# fpga22-serdes-power.net
KiCad netlist of a schematic drawn in Altium Designer
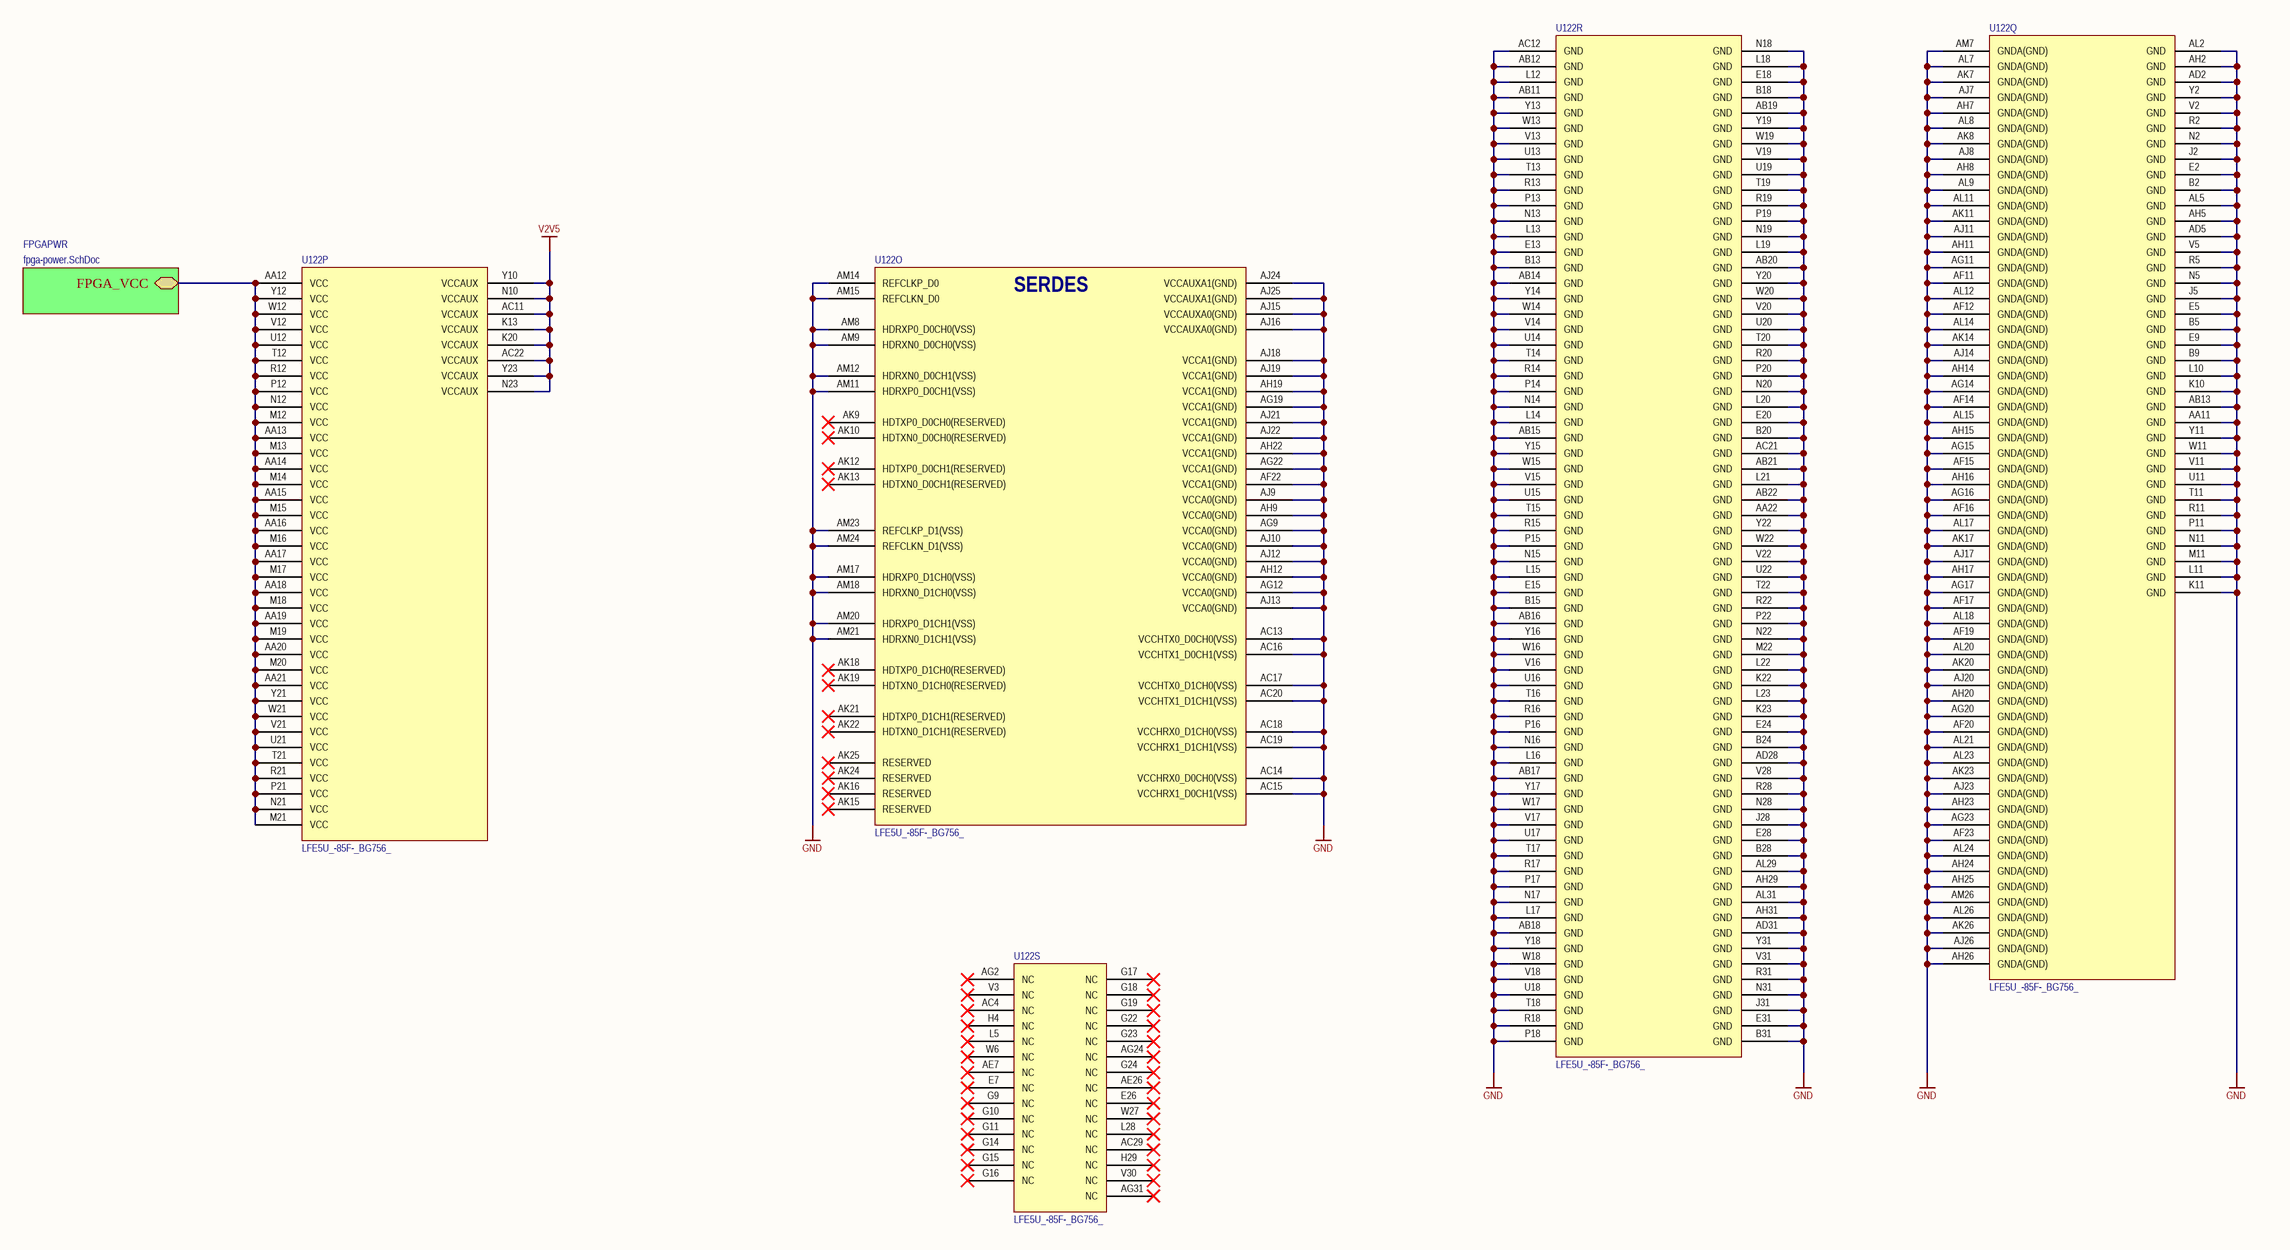
[diagram p0: fpga22-serdes-power.SchDoc]

(export (version "E")
  (design (tool "Eeschema 10.0.6"))
  (components
    (comp (ref "U122")
      (value "LFE5U_-85F-_BG756_")
      (footprint "lattice:caBGA756")
      (description "ECP5 FPGA, 85k LUT, 756-caBGA")
      (fields (field (name "MANUFACTURER") "Lattice Semiconductor"))
      (libsource (lib "lattice") (part "LFE5U_-85F-_BG756_"))
    )
  )
  (nets
    (net (code "1") (name "/FPGA_VCC") (class "Default")
      (node (ref "U122") (pin "AA12") (pinfunction "VCC_AA12") (pintype "power_in"))
      (node (ref "U122") (pin "AA13") (pinfunction "VCC_AA13") (pintype "power_in"))
      (node (ref "U122") (pin "AA14") (pinfunction "VCC_AA14") (pintype "power_in"))
      (node (ref "U122") (pin "AA15") (pinfunction "VCC_AA15") (pintype "power_in"))
      (node (ref "U122") (pin "AA16") (pinfunction "VCC_AA16") (pintype "power_in"))
      (node (ref "U122") (pin "AA17") (pinfunction "VCC_AA17") (pintype "power_in"))
      (node (ref "U122") (pin "AA18") (pinfunction "VCC_AA18") (pintype "power_in"))
      (node (ref "U122") (pin "AA19") (pinfunction "VCC_AA19") (pintype "power_in"))
      (node (ref "U122") (pin "AA20") (pinfunction "VCC_AA20") (pintype "power_in"))
      (node (ref "U122") (pin "AA21") (pinfunction "VCC_AA21") (pintype "power_in"))
      (node (ref "U122") (pin "M12") (pinfunction "VCC_M12") (pintype "power_in"))
      (node (ref "U122") (pin "M13") (pinfunction "VCC_M13") (pintype "power_in"))
      (node (ref "U122") (pin "M14") (pinfunction "VCC_M14") (pintype "power_in"))
      (node (ref "U122") (pin "M15") (pinfunction "VCC_M15") (pintype "power_in"))
      (node (ref "U122") (pin "M16") (pinfunction "VCC_M16") (pintype "power_in"))
      (node (ref "U122") (pin "M17") (pinfunction "VCC_M17") (pintype "power_in"))
      (node (ref "U122") (pin "M18") (pinfunction "VCC_M18") (pintype "power_in"))
      (node (ref "U122") (pin "M19") (pinfunction "VCC_M19") (pintype "power_in"))
      (node (ref "U122") (pin "M20") (pinfunction "VCC_M20") (pintype "power_in"))
      (node (ref "U122") (pin "M21") (pinfunction "VCC_M21") (pintype "power_in"))
      (node (ref "U122") (pin "N12") (pinfunction "VCC_N12") (pintype "power_in"))
      (node (ref "U122") (pin "N21") (pinfunction "VCC_N21") (pintype "power_in"))
      (node (ref "U122") (pin "P12") (pinfunction "VCC_P12") (pintype "power_in"))
      (node (ref "U122") (pin "P21") (pinfunction "VCC_P21") (pintype "power_in"))
      (node (ref "U122") (pin "R12") (pinfunction "VCC_R12") (pintype "power_in"))
      (node (ref "U122") (pin "R21") (pinfunction "VCC_R21") (pintype "power_in"))
      (node (ref "U122") (pin "T12") (pinfunction "VCC_T12") (pintype "power_in"))
      (node (ref "U122") (pin "T21") (pinfunction "VCC_T21") (pintype "power_in"))
      (node (ref "U122") (pin "U12") (pinfunction "VCC_U12") (pintype "power_in"))
      (node (ref "U122") (pin "U21") (pinfunction "VCC_U21") (pintype "power_in"))
      (node (ref "U122") (pin "V12") (pinfunction "VCC_V12") (pintype "power_in"))
      (node (ref "U122") (pin "V21") (pinfunction "VCC_V21") (pintype "power_in"))
      (node (ref "U122") (pin "W12") (pinfunction "VCC_W12") (pintype "power_in"))
      (node (ref "U122") (pin "W21") (pinfunction "VCC_W21") (pintype "power_in"))
      (node (ref "U122") (pin "Y12") (pinfunction "VCC_Y12") (pintype "power_in"))
      (node (ref "U122") (pin "Y21") (pinfunction "VCC_Y21") (pintype "power_in"))
    )
    (net (code "2") (name "GND") (class "Default")
      (node (ref "U122") (pin "AA11") (pinfunction "GND_AA11") (pintype "power_in"))
      (node (ref "U122") (pin "AA22") (pinfunction "GND_AA22") (pintype "power_in"))
      (node (ref "U122") (pin "AB11") (pinfunction "GND_AB11") (pintype "power_in"))
      (node (ref "U122") (pin "AB12") (pinfunction "GND_AB12") (pintype "power_in"))
      (node (ref "U122") (pin "AB13") (pinfunction "GND_AB13") (pintype "power_in"))
      (node (ref "U122") (pin "AB14") (pinfunction "GND_AB14") (pintype "power_in"))
      (node (ref "U122") (pin "AB15") (pinfunction "GND_AB15") (pintype "power_in"))
      (node (ref "U122") (pin "AB16") (pinfunction "GND_AB16") (pintype "power_in"))
      (node (ref "U122") (pin "AB17") (pinfunction "GND_AB17") (pintype "power_in"))
      (node (ref "U122") (pin "AB18") (pinfunction "GND_AB18") (pintype "power_in"))
      (node (ref "U122") (pin "AB19") (pinfunction "GND_AB19") (pintype "power_in"))
      (node (ref "U122") (pin "AB20") (pinfunction "GND_AB20") (pintype "power_in"))
      (node (ref "U122") (pin "AB21") (pinfunction "GND_AB21") (pintype "power_in"))
      (node (ref "U122") (pin "AB22") (pinfunction "GND_AB22") (pintype "power_in"))
      (node (ref "U122") (pin "AC12") (pinfunction "GND_AC12") (pintype "power_in"))
      (node (ref "U122") (pin "AC13") (pinfunction "VCCHTX0_D0CH0(VSS)_AC13") (pintype "power_in"))
      (node (ref "U122") (pin "AC14") (pinfunction "VCCHRX0_D0CH0(VSS)_AC14") (pintype "power_in"))
      (node (ref "U122") (pin "AC15") (pinfunction "VCCHRX1_D0CH1(VSS)_AC15") (pintype "power_in"))
      (node (ref "U122") (pin "AC16") (pinfunction "VCCHTX1_D0CH1(VSS)_AC16") (pintype "power_in"))
      (node (ref "U122") (pin "AC17") (pinfunction "VCCHTX0_D1CH0(VSS)_AC17") (pintype "power_in"))
      (node (ref "U122") (pin "AC18") (pinfunction "VCCHRX0_D1CH0(VSS)_AC18") (pintype "power_in"))
      (node (ref "U122") (pin "AC19") (pinfunction "VCCHRX1_D1CH1(VSS)_AC19") (pintype "power_in"))
      (node (ref "U122") (pin "AC20") (pinfunction "VCCHTX1_D1CH1(VSS)_AC20") (pintype "power_in"))
      (node (ref "U122") (pin "AC21") (pinfunction "GND_AC21") (pintype "power_in"))
      (node (ref "U122") (pin "AD2") (pinfunction "GND_AD2") (pintype "power_in"))
      (node (ref "U122") (pin "AD28") (pinfunction "GND_AD28") (pintype "power_in"))
      (node (ref "U122") (pin "AD31") (pinfunction "GND_AD31") (pintype "power_in"))
      (node (ref "U122") (pin "AD5") (pinfunction "GND_AD5") (pintype "power_in"))
      (node (ref "U122") (pin "AF11") (pinfunction "GNDA(GND)_AF11") (pintype "power_in"))
      (node (ref "U122") (pin "AF12") (pinfunction "GNDA(GND)_AF12") (pintype "power_in"))
      (node (ref "U122") (pin "AF14") (pinfunction "GNDA(GND)_AF14") (pintype "power_in"))
      (node (ref "U122") (pin "AF15") (pinfunction "GNDA(GND)_AF15") (pintype "power_in"))
      (node (ref "U122") (pin "AF16") (pinfunction "GNDA(GND)_AF16") (pintype "power_in"))
      (node (ref "U122") (pin "AF17") (pinfunction "GNDA(GND)_AF17") (pintype "power_in"))
      (node (ref "U122") (pin "AF19") (pinfunction "GNDA(GND)_AF19") (pintype "power_in"))
      (node (ref "U122") (pin "AF20") (pinfunction "GNDA(GND)_AF20") (pintype "power_in"))
      (node (ref "U122") (pin "AF22") (pinfunction "VCCA1(GND)_AF22") (pintype "power_in"))
      (node (ref "U122") (pin "AF23") (pinfunction "GNDA(GND)_AF23") (pintype "power_in"))
      (node (ref "U122") (pin "AG11") (pinfunction "GNDA(GND)_AG11") (pintype "power_in"))
      (node (ref "U122") (pin "AG12") (pinfunction "VCCA0(GND)_AG12") (pintype "power_in"))
      (node (ref "U122") (pin "AG14") (pinfunction "GNDA(GND)_AG14") (pintype "power_in"))
      (node (ref "U122") (pin "AG15") (pinfunction "GNDA(GND)_AG15") (pintype "power_in"))
      (node (ref "U122") (pin "AG16") (pinfunction "GNDA(GND)_AG16") (pintype "power_in"))
      (node (ref "U122") (pin "AG17") (pinfunction "GNDA(GND)_AG17") (pintype "power_in"))
      (node (ref "U122") (pin "AG19") (pinfunction "VCCA1(GND)_AG19") (pintype "power_in"))
      (node (ref "U122") (pin "AG20") (pinfunction "GNDA(GND)_AG20") (pintype "power_in"))
      (node (ref "U122") (pin "AG22") (pinfunction "VCCA1(GND)_AG22") (pintype "power_in"))
      (node (ref "U122") (pin "AG23") (pinfunction "GNDA(GND)_AG23") (pintype "power_in"))
      (node (ref "U122") (pin "AG9") (pinfunction "VCCA0(GND)_AG9") (pintype "power_in"))
      (node (ref "U122") (pin "AH11") (pinfunction "GNDA(GND)_AH11") (pintype "power_in"))
      (node (ref "U122") (pin "AH12") (pinfunction "VCCA0(GND)_AH12") (pintype "power_in"))
      (node (ref "U122") (pin "AH14") (pinfunction "GNDA(GND)_AH14") (pintype "power_in"))
      (node (ref "U122") (pin "AH15") (pinfunction "GNDA(GND)_AH15") (pintype "power_in"))
      (node (ref "U122") (pin "AH16") (pinfunction "GNDA(GND)_AH16") (pintype "power_in"))
      (node (ref "U122") (pin "AH17") (pinfunction "GNDA(GND)_AH17") (pintype "power_in"))
      (node (ref "U122") (pin "AH19") (pinfunction "VCCA1(GND)_AH19") (pintype "power_in"))
      (node (ref "U122") (pin "AH2") (pinfunction "GND_AH2") (pintype "power_in"))
      (node (ref "U122") (pin "AH20") (pinfunction "GNDA(GND)_AH20") (pintype "power_in"))
      (node (ref "U122") (pin "AH22") (pinfunction "VCCA1(GND)_AH22") (pintype "power_in"))
      (node (ref "U122") (pin "AH23") (pinfunction "GNDA(GND)_AH23") (pintype "power_in"))
      (node (ref "U122") (pin "AH24") (pinfunction "GNDA(GND)_AH24") (pintype "power_in"))
      (node (ref "U122") (pin "AH25") (pinfunction "GNDA(GND)_AH25") (pintype "power_in"))
      (node (ref "U122") (pin "AH26") (pinfunction "GNDA(GND)_AH26") (pintype "power_in"))
      (node (ref "U122") (pin "AH29") (pinfunction "GND_AH29") (pintype "power_in"))
      (node (ref "U122") (pin "AH31") (pinfunction "GND_AH31") (pintype "power_in"))
      (node (ref "U122") (pin "AH5") (pinfunction "GND_AH5") (pintype "power_in"))
      (node (ref "U122") (pin "AH7") (pinfunction "GNDA(GND)_AH7") (pintype "power_in"))
      (node (ref "U122") (pin "AH8") (pinfunction "GNDA(GND)_AH8") (pintype "power_in"))
      (node (ref "U122") (pin "AH9") (pinfunction "VCCA0(GND)_AH9") (pintype "power_in"))
      (node (ref "U122") (pin "AJ10") (pinfunction "VCCA0(GND)_AJ10") (pintype "power_in"))
      (node (ref "U122") (pin "AJ11") (pinfunction "GNDA(GND)_AJ11") (pintype "power_in"))
      (node (ref "U122") (pin "AJ12") (pinfunction "VCCA0(GND)_AJ12") (pintype "power_in"))
      (node (ref "U122") (pin "AJ13") (pinfunction "VCCA0(GND)_AJ13") (pintype "power_in"))
      (node (ref "U122") (pin "AJ14") (pinfunction "GNDA(GND)_AJ14") (pintype "power_in"))
      (node (ref "U122") (pin "AJ15") (pinfunction "VCCAUXA0(GND)_AJ15") (pintype "power_in"))
      (node (ref "U122") (pin "AJ16") (pinfunction "VCCAUXA0(GND)_AJ16") (pintype "power_in"))
      (node (ref "U122") (pin "AJ17") (pinfunction "GNDA(GND)_AJ17") (pintype "power_in"))
      (node (ref "U122") (pin "AJ18") (pinfunction "VCCA1(GND)_AJ18") (pintype "power_in"))
      (node (ref "U122") (pin "AJ19") (pinfunction "VCCA1(GND)_AJ19") (pintype "power_in"))
      (node (ref "U122") (pin "AJ20") (pinfunction "GNDA(GND)_AJ20") (pintype "power_in"))
      (node (ref "U122") (pin "AJ21") (pinfunction "VCCA1(GND)_AJ21") (pintype "power_in"))
      (node (ref "U122") (pin "AJ22") (pinfunction "VCCA1(GND)_AJ22") (pintype "power_in"))
      (node (ref "U122") (pin "AJ23") (pinfunction "GNDA(GND)_AJ23") (pintype "power_in"))
      (node (ref "U122") (pin "AJ24") (pinfunction "VCCAUXA1(GND)_AJ24") (pintype "power_in"))
      (node (ref "U122") (pin "AJ25") (pinfunction "VCCAUXA1(GND)_AJ25") (pintype "power_in"))
      (node (ref "U122") (pin "AJ26") (pinfunction "GNDA(GND)_AJ26") (pintype "power_in"))
      (node (ref "U122") (pin "AJ7") (pinfunction "GNDA(GND)_AJ7") (pintype "power_in"))
      (node (ref "U122") (pin "AJ8") (pinfunction "GNDA(GND)_AJ8") (pintype "power_in"))
      (node (ref "U122") (pin "AJ9") (pinfunction "VCCA0(GND)_AJ9") (pintype "power_in"))
      (node (ref "U122") (pin "AK11") (pinfunction "GNDA(GND)_AK11") (pintype "power_in"))
      (node (ref "U122") (pin "AK14") (pinfunction "GNDA(GND)_AK14") (pintype "power_in"))
      (node (ref "U122") (pin "AK17") (pinfunction "GNDA(GND)_AK17") (pintype "power_in"))
      (node (ref "U122") (pin "AK20") (pinfunction "GNDA(GND)_AK20") (pintype "power_in"))
      (node (ref "U122") (pin "AK23") (pinfunction "GNDA(GND)_AK23") (pintype "power_in"))
      (node (ref "U122") (pin "AK26") (pinfunction "GNDA(GND)_AK26") (pintype "power_in"))
      (node (ref "U122") (pin "AK7") (pinfunction "GNDA(GND)_AK7") (pintype "power_in"))
      (node (ref "U122") (pin "AK8") (pinfunction "GNDA(GND)_AK8") (pintype "power_in"))
      (node (ref "U122") (pin "AL11") (pinfunction "GNDA(GND)_AL11") (pintype "power_in"))
      (node (ref "U122") (pin "AL12") (pinfunction "GNDA(GND)_AL12") (pintype "power_in"))
      (node (ref "U122") (pin "AL14") (pinfunction "GNDA(GND)_AL14") (pintype "power_in"))
      (node (ref "U122") (pin "AL15") (pinfunction "GNDA(GND)_AL15") (pintype "power_in"))
      (node (ref "U122") (pin "AL17") (pinfunction "GNDA(GND)_AL17") (pintype "power_in"))
      (node (ref "U122") (pin "AL18") (pinfunction "GNDA(GND)_AL18") (pintype "power_in"))
      (node (ref "U122") (pin "AL2") (pinfunction "GND_AL2") (pintype "power_in"))
      (node (ref "U122") (pin "AL20") (pinfunction "GNDA(GND)_AL20") (pintype "power_in"))
      (node (ref "U122") (pin "AL21") (pinfunction "GNDA(GND)_AL21") (pintype "power_in"))
      (node (ref "U122") (pin "AL23") (pinfunction "GNDA(GND)_AL23") (pintype "power_in"))
      (node (ref "U122") (pin "AL24") (pinfunction "GNDA(GND)_AL24") (pintype "power_in"))
      (node (ref "U122") (pin "AL26") (pinfunction "GNDA(GND)_AL26") (pintype "power_in"))
      (node (ref "U122") (pin "AL29") (pinfunction "GND_AL29") (pintype "power_in"))
      (node (ref "U122") (pin "AL31") (pinfunction "GND_AL31") (pintype "power_in"))
      (node (ref "U122") (pin "AL5") (pinfunction "GND_AL5") (pintype "power_in"))
      (node (ref "U122") (pin "AL7") (pinfunction "GNDA(GND)_AL7") (pintype "power_in"))
      (node (ref "U122") (pin "AL8") (pinfunction "GNDA(GND)_AL8") (pintype "power_in"))
      (node (ref "U122") (pin "AL9") (pinfunction "GNDA(GND)_AL9") (pintype "power_in"))
      (node (ref "U122") (pin "AM11") (pinfunction "HDRXP0_D0CH1(VSS)_AM11") (pintype "passive"))
      (node (ref "U122") (pin "AM12") (pinfunction "HDRXN0_D0CH1(VSS)_AM12") (pintype "passive"))
      (node (ref "U122") (pin "AM14") (pinfunction "REFCLKP_D0_AM14") (pintype "passive"))
      (node (ref "U122") (pin "AM15") (pinfunction "REFCLKN_D0_AM15") (pintype "passive"))
      (node (ref "U122") (pin "AM17") (pinfunction "HDRXP0_D1CH0(VSS)_AM17") (pintype "passive"))
      (node (ref "U122") (pin "AM18") (pinfunction "HDRXN0_D1CH0(VSS)_AM18") (pintype "passive"))
      (node (ref "U122") (pin "AM20") (pinfunction "HDRXP0_D1CH1(VSS)_AM20") (pintype "passive"))
      (node (ref "U122") (pin "AM21") (pinfunction "HDRXN0_D1CH1(VSS)_AM21") (pintype "passive"))
      (node (ref "U122") (pin "AM23") (pinfunction "REFCLKP_D1(VSS)_AM23") (pintype "passive"))
      (node (ref "U122") (pin "AM24") (pinfunction "REFCLKN_D1(VSS)_AM24") (pintype "passive"))
      (node (ref "U122") (pin "AM26") (pinfunction "GNDA(GND)_AM26") (pintype "power_in"))
      (node (ref "U122") (pin "AM7") (pinfunction "GNDA(GND)_AM7") (pintype "power_in"))
      (node (ref "U122") (pin "AM8") (pinfunction "HDRXP0_D0CH0(VSS)_AM8") (pintype "passive"))
      (node (ref "U122") (pin "AM9") (pinfunction "HDRXN0_D0CH0(VSS)_AM9") (pintype "passive"))
      (node (ref "U122") (pin "B13") (pinfunction "GND_B13") (pintype "power_in"))
      (node (ref "U122") (pin "B15") (pinfunction "GND_B15") (pintype "power_in"))
      (node (ref "U122") (pin "B18") (pinfunction "GND_B18") (pintype "power_in"))
      (node (ref "U122") (pin "B2") (pinfunction "GND_B2") (pintype "power_in"))
      (node (ref "U122") (pin "B20") (pinfunction "GND_B20") (pintype "power_in"))
      (node (ref "U122") (pin "B24") (pinfunction "GND_B24") (pintype "power_in"))
      (node (ref "U122") (pin "B28") (pinfunction "GND_B28") (pintype "power_in"))
      (node (ref "U122") (pin "B31") (pinfunction "GND_B31") (pintype "power_in"))
      (node (ref "U122") (pin "B5") (pinfunction "GND_B5") (pintype "power_in"))
      (node (ref "U122") (pin "B9") (pinfunction "GND_B9") (pintype "power_in"))
      (node (ref "U122") (pin "E13") (pinfunction "GND_E13") (pintype "power_in"))
      (node (ref "U122") (pin "E15") (pinfunction "GND_E15") (pintype "power_in"))
      (node (ref "U122") (pin "E18") (pinfunction "GND_E18") (pintype "power_in"))
      (node (ref "U122") (pin "E2") (pinfunction "GND_E2") (pintype "power_in"))
      (node (ref "U122") (pin "E20") (pinfunction "GND_E20") (pintype "power_in"))
      (node (ref "U122") (pin "E24") (pinfunction "GND_E24") (pintype "power_in"))
      (node (ref "U122") (pin "E28") (pinfunction "GND_E28") (pintype "power_in"))
      (node (ref "U122") (pin "E31") (pinfunction "GND_E31") (pintype "power_in"))
      (node (ref "U122") (pin "E5") (pinfunction "GND_E5") (pintype "power_in"))
      (node (ref "U122") (pin "E9") (pinfunction "GND_E9") (pintype "power_in"))
      (node (ref "U122") (pin "J2") (pinfunction "GND_J2") (pintype "power_in"))
      (node (ref "U122") (pin "J28") (pinfunction "GND_J28") (pintype "power_in"))
      (node (ref "U122") (pin "J31") (pinfunction "GND_J31") (pintype "power_in"))
      (node (ref "U122") (pin "J5") (pinfunction "GND_J5") (pintype "power_in"))
      (node (ref "U122") (pin "K10") (pinfunction "GND_K10") (pintype "power_in"))
      (node (ref "U122") (pin "K11") (pinfunction "GND_K11") (pintype "power_in"))
      (node (ref "U122") (pin "K22") (pinfunction "GND_K22") (pintype "power_in"))
      (node (ref "U122") (pin "K23") (pinfunction "GND_K23") (pintype "power_in"))
      (node (ref "U122") (pin "L10") (pinfunction "GND_L10") (pintype "power_in"))
      (node (ref "U122") (pin "L11") (pinfunction "GND_L11") (pintype "power_in"))
      (node (ref "U122") (pin "L12") (pinfunction "GND_L12") (pintype "power_in"))
      (node (ref "U122") (pin "L13") (pinfunction "GND_L13") (pintype "power_in"))
      (node (ref "U122") (pin "L14") (pinfunction "GND_L14") (pintype "power_in"))
      (node (ref "U122") (pin "L15") (pinfunction "GND_L15") (pintype "power_in"))
      (node (ref "U122") (pin "L16") (pinfunction "GND_L16") (pintype "power_in"))
      (node (ref "U122") (pin "L17") (pinfunction "GND_L17") (pintype "power_in"))
      (node (ref "U122") (pin "L18") (pinfunction "GND_L18") (pintype "power_in"))
      (node (ref "U122") (pin "L19") (pinfunction "GND_L19") (pintype "power_in"))
      (node (ref "U122") (pin "L20") (pinfunction "GND_L20") (pintype "power_in"))
      (node (ref "U122") (pin "L21") (pinfunction "GND_L21") (pintype "power_in"))
      (node (ref "U122") (pin "L22") (pinfunction "GND_L22") (pintype "power_in"))
      (node (ref "U122") (pin "L23") (pinfunction "GND_L23") (pintype "power_in"))
      (node (ref "U122") (pin "M11") (pinfunction "GND_M11") (pintype "power_in"))
      (node (ref "U122") (pin "M22") (pinfunction "GND_M22") (pintype "power_in"))
      (node (ref "U122") (pin "N11") (pinfunction "GND_N11") (pintype "power_in"))
      (node (ref "U122") (pin "N13") (pinfunction "GND_N13") (pintype "power_in"))
      (node (ref "U122") (pin "N14") (pinfunction "GND_N14") (pintype "power_in"))
      (node (ref "U122") (pin "N15") (pinfunction "GND_N15") (pintype "power_in"))
      (node (ref "U122") (pin "N16") (pinfunction "GND_N16") (pintype "power_in"))
      (node (ref "U122") (pin "N17") (pinfunction "GND_N17") (pintype "power_in"))
      (node (ref "U122") (pin "N18") (pinfunction "GND_N18") (pintype "power_in"))
      (node (ref "U122") (pin "N19") (pinfunction "GND_N19") (pintype "power_in"))
      (node (ref "U122") (pin "N2") (pinfunction "GND_N2") (pintype "power_in"))
      (node (ref "U122") (pin "N20") (pinfunction "GND_N20") (pintype "power_in"))
      (node (ref "U122") (pin "N22") (pinfunction "GND_N22") (pintype "power_in"))
      (node (ref "U122") (pin "N28") (pinfunction "GND_N28") (pintype "power_in"))
      (node (ref "U122") (pin "N31") (pinfunction "GND_N31") (pintype "power_in"))
      (node (ref "U122") (pin "N5") (pinfunction "GND_N5") (pintype "power_in"))
      (node (ref "U122") (pin "P11") (pinfunction "GND_P11") (pintype "power_in"))
      (node (ref "U122") (pin "P13") (pinfunction "GND_P13") (pintype "power_in"))
      (node (ref "U122") (pin "P14") (pinfunction "GND_P14") (pintype "power_in"))
      (node (ref "U122") (pin "P15") (pinfunction "GND_P15") (pintype "power_in"))
      (node (ref "U122") (pin "P16") (pinfunction "GND_P16") (pintype "power_in"))
      (node (ref "U122") (pin "P17") (pinfunction "GND_P17") (pintype "power_in"))
      (node (ref "U122") (pin "P18") (pinfunction "GND_P18") (pintype "power_in"))
      (node (ref "U122") (pin "P19") (pinfunction "GND_P19") (pintype "power_in"))
      (node (ref "U122") (pin "P20") (pinfunction "GND_P20") (pintype "power_in"))
      (node (ref "U122") (pin "P22") (pinfunction "GND_P22") (pintype "power_in"))
      (node (ref "U122") (pin "R11") (pinfunction "GND_R11") (pintype "power_in"))
      (node (ref "U122") (pin "R13") (pinfunction "GND_R13") (pintype "power_in"))
      (node (ref "U122") (pin "R14") (pinfunction "GND_R14") (pintype "power_in"))
      (node (ref "U122") (pin "R15") (pinfunction "GND_R15") (pintype "power_in"))
      (node (ref "U122") (pin "R16") (pinfunction "GND_R16") (pintype "power_in"))
      (node (ref "U122") (pin "R17") (pinfunction "GND_R17") (pintype "power_in"))
      (node (ref "U122") (pin "R18") (pinfunction "GND_R18") (pintype "power_in"))
      (node (ref "U122") (pin "R19") (pinfunction "GND_R19") (pintype "power_in"))
      (node (ref "U122") (pin "R2") (pinfunction "GND_R2") (pintype "power_in"))
      (node (ref "U122") (pin "R20") (pinfunction "GND_R20") (pintype "power_in"))
      (node (ref "U122") (pin "R22") (pinfunction "GND_R22") (pintype "power_in"))
      (node (ref "U122") (pin "R28") (pinfunction "GND_R28") (pintype "power_in"))
      (node (ref "U122") (pin "R31") (pinfunction "GND_R31") (pintype "power_in"))
      (node (ref "U122") (pin "R5") (pinfunction "GND_R5") (pintype "power_in"))
      (node (ref "U122") (pin "T11") (pinfunction "GND_T11") (pintype "power_in"))
      (node (ref "U122") (pin "T13") (pinfunction "GND_T13") (pintype "power_in"))
      (node (ref "U122") (pin "T14") (pinfunction "GND_T14") (pintype "power_in"))
      (node (ref "U122") (pin "T15") (pinfunction "GND_T15") (pintype "power_in"))
      (node (ref "U122") (pin "T16") (pinfunction "GND_T16") (pintype "power_in"))
      (node (ref "U122") (pin "T17") (pinfunction "GND_T17") (pintype "power_in"))
      (node (ref "U122") (pin "T18") (pinfunction "GND_T18") (pintype "power_in"))
      (node (ref "U122") (pin "T19") (pinfunction "GND_T19") (pintype "power_in"))
      (node (ref "U122") (pin "T20") (pinfunction "GND_T20") (pintype "power_in"))
      (node (ref "U122") (pin "T22") (pinfunction "GND_T22") (pintype "power_in"))
      (node (ref "U122") (pin "U11") (pinfunction "GND_U11") (pintype "power_in"))
      (node (ref "U122") (pin "U13") (pinfunction "GND_U13") (pintype "power_in"))
      (node (ref "U122") (pin "U14") (pinfunction "GND_U14") (pintype "power_in"))
      (node (ref "U122") (pin "U15") (pinfunction "GND_U15") (pintype "power_in"))
      (node (ref "U122") (pin "U16") (pinfunction "GND_U16") (pintype "power_in"))
      (node (ref "U122") (pin "U17") (pinfunction "GND_U17") (pintype "power_in"))
      (node (ref "U122") (pin "U18") (pinfunction "GND_U18") (pintype "power_in"))
      (node (ref "U122") (pin "U19") (pinfunction "GND_U19") (pintype "power_in"))
      (node (ref "U122") (pin "U20") (pinfunction "GND_U20") (pintype "power_in"))
      (node (ref "U122") (pin "U22") (pinfunction "GND_U22") (pintype "power_in"))
      (node (ref "U122") (pin "V11") (pinfunction "GND_V11") (pintype "power_in"))
      (node (ref "U122") (pin "V13") (pinfunction "GND_V13") (pintype "power_in"))
      (node (ref "U122") (pin "V14") (pinfunction "GND_V14") (pintype "power_in"))
      (node (ref "U122") (pin "V15") (pinfunction "GND_V15") (pintype "power_in"))
      (node (ref "U122") (pin "V16") (pinfunction "GND_V16") (pintype "power_in"))
      (node (ref "U122") (pin "V17") (pinfunction "GND_V17") (pintype "power_in"))
      (node (ref "U122") (pin "V18") (pinfunction "GND_V18") (pintype "power_in"))
      (node (ref "U122") (pin "V19") (pinfunction "GND_V19") (pintype "power_in"))
      (node (ref "U122") (pin "V2") (pinfunction "GND_V2") (pintype "power_in"))
      (node (ref "U122") (pin "V20") (pinfunction "GND_V20") (pintype "power_in"))
      (node (ref "U122") (pin "V22") (pinfunction "GND_V22") (pintype "power_in"))
      (node (ref "U122") (pin "V28") (pinfunction "GND_V28") (pintype "power_in"))
      (node (ref "U122") (pin "V31") (pinfunction "GND_V31") (pintype "power_in"))
      (node (ref "U122") (pin "V5") (pinfunction "GND_V5") (pintype "power_in"))
      (node (ref "U122") (pin "W11") (pinfunction "GND_W11") (pintype "power_in"))
      (node (ref "U122") (pin "W13") (pinfunction "GND_W13") (pintype "power_in"))
      (node (ref "U122") (pin "W14") (pinfunction "GND_W14") (pintype "power_in"))
      (node (ref "U122") (pin "W15") (pinfunction "GND_W15") (pintype "power_in"))
      (node (ref "U122") (pin "W16") (pinfunction "GND_W16") (pintype "power_in"))
      (node (ref "U122") (pin "W17") (pinfunction "GND_W17") (pintype "power_in"))
      (node (ref "U122") (pin "W18") (pinfunction "GND_W18") (pintype "power_in"))
      (node (ref "U122") (pin "W19") (pinfunction "GND_W19") (pintype "power_in"))
      (node (ref "U122") (pin "W20") (pinfunction "GND_W20") (pintype "power_in"))
      (node (ref "U122") (pin "W22") (pinfunction "GND_W22") (pintype "power_in"))
      (node (ref "U122") (pin "Y11") (pinfunction "GND_Y11") (pintype "power_in"))
      (node (ref "U122") (pin "Y13") (pinfunction "GND_Y13") (pintype "power_in"))
      (node (ref "U122") (pin "Y14") (pinfunction "GND_Y14") (pintype "power_in"))
      (node (ref "U122") (pin "Y15") (pinfunction "GND_Y15") (pintype "power_in"))
      (node (ref "U122") (pin "Y16") (pinfunction "GND_Y16") (pintype "power_in"))
      (node (ref "U122") (pin "Y17") (pinfunction "GND_Y17") (pintype "power_in"))
      (node (ref "U122") (pin "Y18") (pinfunction "GND_Y18") (pintype "power_in"))
      (node (ref "U122") (pin "Y19") (pinfunction "GND_Y19") (pintype "power_in"))
      (node (ref "U122") (pin "Y2") (pinfunction "GND_Y2") (pintype "power_in"))
      (node (ref "U122") (pin "Y20") (pinfunction "GND_Y20") (pintype "power_in"))
      (node (ref "U122") (pin "Y22") (pinfunction "GND_Y22") (pintype "power_in"))
      (node (ref "U122") (pin "Y31") (pinfunction "GND_Y31") (pintype "power_in"))
    )
    (net (code "3") (name "V2V5") (class "Default")
      (node (ref "U122") (pin "AC11") (pinfunction "VCCAUX_AC11") (pintype "power_in"))
      (node (ref "U122") (pin "AC22") (pinfunction "VCCAUX_AC22") (pintype "power_in"))
      (node (ref "U122") (pin "K13") (pinfunction "VCCAUX_K13") (pintype "power_in"))
      (node (ref "U122") (pin "K20") (pinfunction "VCCAUX_K20") (pintype "power_in"))
      (node (ref "U122") (pin "N10") (pinfunction "VCCAUX_N10") (pintype "power_in"))
      (node (ref "U122") (pin "N23") (pinfunction "VCCAUX_N23") (pintype "power_in"))
      (node (ref "U122") (pin "Y10") (pinfunction "VCCAUX_Y10") (pintype "power_in"))
      (node (ref "U122") (pin "Y23") (pinfunction "VCCAUX_Y23") (pintype "power_in"))
    )
    (net (code "4") (name "unconnected-(U122O-HDTXN0_D0CH0(RESERVED)-PadAK10)") (class "Default")
      (node (ref "U122") (pin "AK10") (pinfunction "HDTXN0_D0CH0(RESERVED)_AK10") (pintype "passive+no_connect"))
    )
    (net (code "5") (name "unconnected-(U122O-HDTXN0_D0CH1(RESERVED)-PadAK13)") (class "Default")
      (node (ref "U122") (pin "AK13") (pinfunction "HDTXN0_D0CH1(RESERVED)_AK13") (pintype "passive+no_connect"))
    )
    (net (code "6") (name "unconnected-(U122O-HDTXN0_D1CH0(RESERVED)-PadAK19)") (class "Default")
      (node (ref "U122") (pin "AK19") (pinfunction "HDTXN0_D1CH0(RESERVED)_AK19") (pintype "passive+no_connect"))
    )
    (net (code "7") (name "unconnected-(U122O-HDTXN0_D1CH1(RESERVED)-PadAK22)") (class "Default")
      (node (ref "U122") (pin "AK22") (pinfunction "HDTXN0_D1CH1(RESERVED)_AK22") (pintype "passive+no_connect"))
    )
    (net (code "8") (name "unconnected-(U122O-HDTXP0_D0CH0(RESERVED)-PadAK9)") (class "Default")
      (node (ref "U122") (pin "AK9") (pinfunction "HDTXP0_D0CH0(RESERVED)_AK9") (pintype "passive+no_connect"))
    )
    (net (code "9") (name "unconnected-(U122O-HDTXP0_D0CH1(RESERVED)-PadAK12)") (class "Default")
      (node (ref "U122") (pin "AK12") (pinfunction "HDTXP0_D0CH1(RESERVED)_AK12") (pintype "passive+no_connect"))
    )
    (net (code "10") (name "unconnected-(U122O-HDTXP0_D1CH0(RESERVED)-PadAK18)") (class "Default")
      (node (ref "U122") (pin "AK18") (pinfunction "HDTXP0_D1CH0(RESERVED)_AK18") (pintype "passive+no_connect"))
    )
    (net (code "11") (name "unconnected-(U122O-HDTXP0_D1CH1(RESERVED)-PadAK21)") (class "Default")
      (node (ref "U122") (pin "AK21") (pinfunction "HDTXP0_D1CH1(RESERVED)_AK21") (pintype "passive+no_connect"))
    )
    (net (code "12") (name "unconnected-(U122O-RESERVED-PadAK15)") (class "Default")
      (node (ref "U122") (pin "AK15") (pinfunction "RESERVED_AK15") (pintype "passive+no_connect"))
    )
    (net (code "13") (name "unconnected-(U122O-RESERVED-PadAK16)") (class "Default")
      (node (ref "U122") (pin "AK16") (pinfunction "RESERVED_AK16") (pintype "passive+no_connect"))
    )
    (net (code "14") (name "unconnected-(U122O-RESERVED-PadAK24)") (class "Default")
      (node (ref "U122") (pin "AK24") (pinfunction "RESERVED_AK24") (pintype "passive+no_connect"))
    )
    (net (code "15") (name "unconnected-(U122O-RESERVED-PadAK25)") (class "Default")
      (node (ref "U122") (pin "AK25") (pinfunction "RESERVED_AK25") (pintype "passive+no_connect"))
    )
    (net (code "16") (name "unconnected-(U122S-NC-PadAC4)") (class "Default")
      (node (ref "U122") (pin "AC4") (pinfunction "NC_AC4") (pintype "passive+no_connect"))
    )
    (net (code "17") (name "unconnected-(U122S-NC-PadAC29)") (class "Default")
      (node (ref "U122") (pin "AC29") (pinfunction "NC_AC29") (pintype "passive+no_connect"))
    )
    (net (code "18") (name "unconnected-(U122S-NC-PadAE7)") (class "Default")
      (node (ref "U122") (pin "AE7") (pinfunction "NC_AE7") (pintype "passive+no_connect"))
    )
    (net (code "19") (name "unconnected-(U122S-NC-PadAE26)") (class "Default")
      (node (ref "U122") (pin "AE26") (pinfunction "NC_AE26") (pintype "passive+no_connect"))
    )
    (net (code "20") (name "unconnected-(U122S-NC-PadAG2)") (class "Default")
      (node (ref "U122") (pin "AG2") (pinfunction "NC_AG2") (pintype "passive+no_connect"))
    )
    (net (code "21") (name "unconnected-(U122S-NC-PadAG24)") (class "Default")
      (node (ref "U122") (pin "AG24") (pinfunction "NC_AG24") (pintype "passive+no_connect"))
    )
    (net (code "22") (name "unconnected-(U122S-NC-PadAG31)") (class "Default")
      (node (ref "U122") (pin "AG31") (pinfunction "NC_AG31") (pintype "passive+no_connect"))
    )
    (net (code "23") (name "unconnected-(U122S-NC-PadE7)") (class "Default")
      (node (ref "U122") (pin "E7") (pinfunction "NC_E7") (pintype "passive+no_connect"))
    )
    (net (code "24") (name "unconnected-(U122S-NC-PadE26)") (class "Default")
      (node (ref "U122") (pin "E26") (pinfunction "NC_E26") (pintype "passive+no_connect"))
    )
    (net (code "25") (name "unconnected-(U122S-NC-PadG9)") (class "Default")
      (node (ref "U122") (pin "G9") (pinfunction "NC_G9") (pintype "passive+no_connect"))
    )
    (net (code "26") (name "unconnected-(U122S-NC-PadG10)") (class "Default")
      (node (ref "U122") (pin "G10") (pinfunction "NC_G10") (pintype "passive+no_connect"))
    )
    (net (code "27") (name "unconnected-(U122S-NC-PadG11)") (class "Default")
      (node (ref "U122") (pin "G11") (pinfunction "NC_G11") (pintype "passive+no_connect"))
    )
    (net (code "28") (name "unconnected-(U122S-NC-PadG14)") (class "Default")
      (node (ref "U122") (pin "G14") (pinfunction "NC_G14") (pintype "passive+no_connect"))
    )
    (net (code "29") (name "unconnected-(U122S-NC-PadG15)") (class "Default")
      (node (ref "U122") (pin "G15") (pinfunction "NC_G15") (pintype "passive+no_connect"))
    )
    (net (code "30") (name "unconnected-(U122S-NC-PadG16)") (class "Default")
      (node (ref "U122") (pin "G16") (pinfunction "NC_G16") (pintype "passive+no_connect"))
    )
    (net (code "31") (name "unconnected-(U122S-NC-PadG17)") (class "Default")
      (node (ref "U122") (pin "G17") (pinfunction "NC_G17") (pintype "passive+no_connect"))
    )
    (net (code "32") (name "unconnected-(U122S-NC-PadG18)") (class "Default")
      (node (ref "U122") (pin "G18") (pinfunction "NC_G18") (pintype "passive+no_connect"))
    )
    (net (code "33") (name "unconnected-(U122S-NC-PadG19)") (class "Default")
      (node (ref "U122") (pin "G19") (pinfunction "NC_G19") (pintype "passive+no_connect"))
    )
    (net (code "34") (name "unconnected-(U122S-NC-PadG22)") (class "Default")
      (node (ref "U122") (pin "G22") (pinfunction "NC_G22") (pintype "passive+no_connect"))
    )
    (net (code "35") (name "unconnected-(U122S-NC-PadG23)") (class "Default")
      (node (ref "U122") (pin "G23") (pinfunction "NC_G23") (pintype "passive+no_connect"))
    )
    (net (code "36") (name "unconnected-(U122S-NC-PadG24)") (class "Default")
      (node (ref "U122") (pin "G24") (pinfunction "NC_G24") (pintype "passive+no_connect"))
    )
    (net (code "37") (name "unconnected-(U122S-NC-PadH4)") (class "Default")
      (node (ref "U122") (pin "H4") (pinfunction "NC_H4") (pintype "passive+no_connect"))
    )
    (net (code "38") (name "unconnected-(U122S-NC-PadH29)") (class "Default")
      (node (ref "U122") (pin "H29") (pinfunction "NC_H29") (pintype "passive+no_connect"))
    )
    (net (code "39") (name "unconnected-(U122S-NC-PadL5)") (class "Default")
      (node (ref "U122") (pin "L5") (pinfunction "NC_L5") (pintype "passive+no_connect"))
    )
    (net (code "40") (name "unconnected-(U122S-NC-PadL28)") (class "Default")
      (node (ref "U122") (pin "L28") (pinfunction "NC_L28") (pintype "passive+no_connect"))
    )
    (net (code "41") (name "unconnected-(U122S-NC-PadV3)") (class "Default")
      (node (ref "U122") (pin "V3") (pinfunction "NC_V3") (pintype "passive+no_connect"))
    )
    (net (code "42") (name "unconnected-(U122S-NC-PadV30)") (class "Default")
      (node (ref "U122") (pin "V30") (pinfunction "NC_V30") (pintype "passive+no_connect"))
    )
    (net (code "43") (name "unconnected-(U122S-NC-PadW6)") (class "Default")
      (node (ref "U122") (pin "W6") (pinfunction "NC_W6") (pintype "passive+no_connect"))
    )
    (net (code "44") (name "unconnected-(U122S-NC-PadW27)") (class "Default")
      (node (ref "U122") (pin "W27") (pinfunction "NC_W27") (pintype "passive+no_connect"))
    )
  )
)
